# SevSeg-Shield-v10.net
KiCad netlist of a schematic drawn in EAGLE
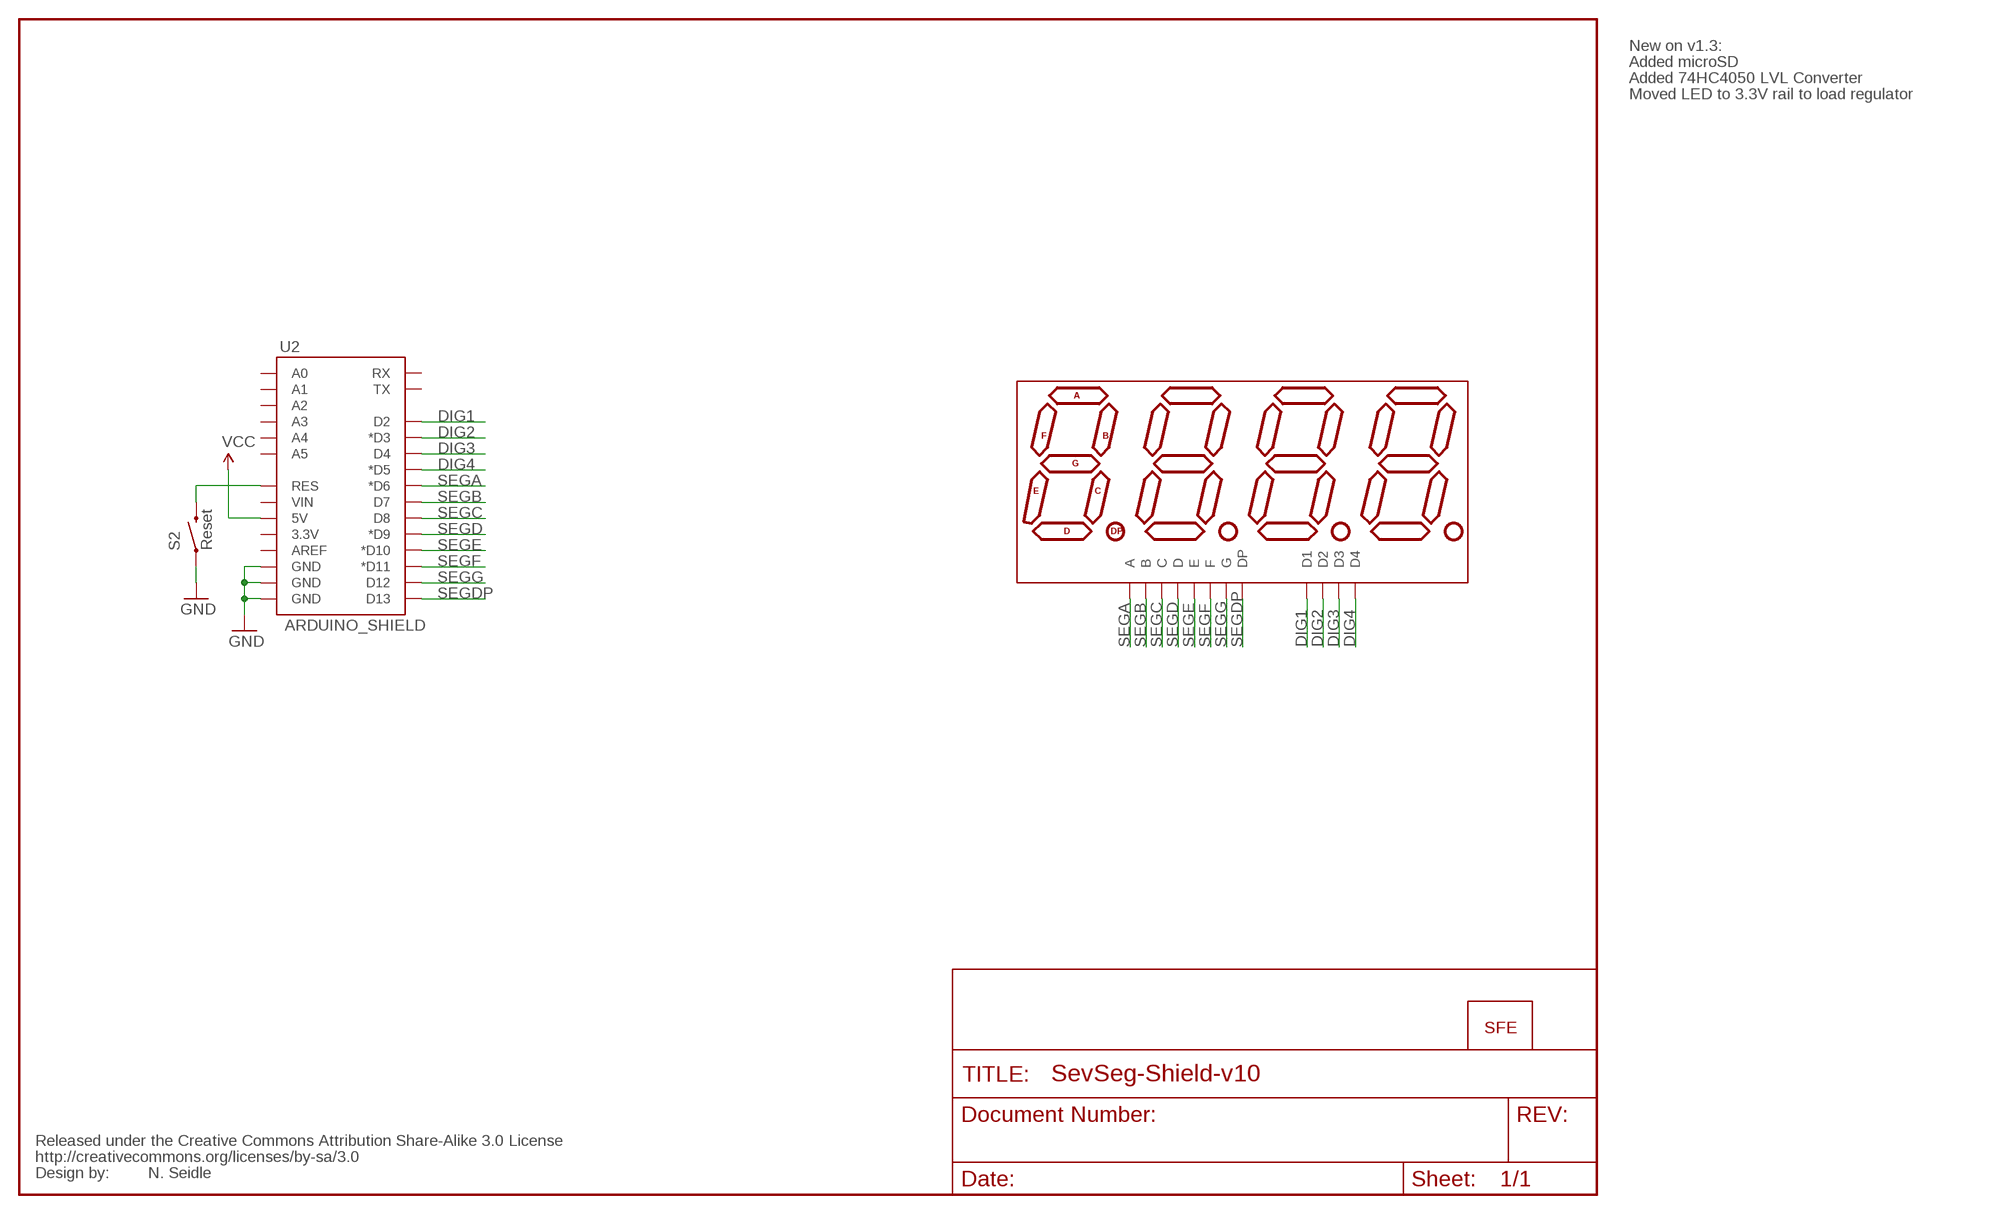
[diagram p0: schematic, sheet 1]

(export (version "E")
  (design (tool "Eeschema 10.0.6"))
  (components
    (comp (ref "S2")
      (value "Reset")
      (footprint "eagle-import:TACTILE-PTH")
      (libsource (lib "eagle-import") (part "SWITCH-MOMENTARY-2PTH"))
    )
    (comp (ref "U$1")
      (value "7-SEGMENT-4DIGIT-COUNTERPTH")
      (footprint "eagle-import:7-SEGMENT-4DIGIT-COUNTER")
      (libsource (lib "eagle-import") (part "7-SEGMENT-4DIGIT-COUNTERPTH"))
    )
    (comp (ref "U$3")
      (value "CREATIVE_COMMONS")
      (footprint "eagle-import:CREATIVE_COMMONS")
      (libsource (lib "eagle-import") (part "CREATIVE_COMMONS"))
    )
    (comp (ref "U$7")
      (value "LOGO-SFENEW")
      (footprint "eagle-import:SFE-NEW-WEBLOGO")
      (libsource (lib "eagle-import") (part "LOGO-SFENEW"))
    )
    (comp (ref "U2")
      (value "ARDUINO_SHIELD")
      (footprint "eagle-import:DUEMILANOVE_SHIELD")
      (libsource (lib "eagle-import") (part "ARDUINO_SHIELDLABEL"))
    )
  )
  (nets
    (net (code "1") (name "/DIG1") (class "Default")
      (node (ref "U$1") (pin "12") (pinfunction "D1_12") (pintype "bidirectional"))
      (node (ref "U2") (pin "D2") (pinfunction "D2_D2") (pintype "bidirectional"))
    )
    (net (code "2") (name "/DIG2") (class "Default")
      (node (ref "U$1") (pin "9") (pinfunction "D2_9") (pintype "bidirectional"))
      (node (ref "U2") (pin "D3") (pinfunction "*D3_D3") (pintype "bidirectional"))
    )
    (net (code "3") (name "/DIG3") (class "Default")
      (node (ref "U$1") (pin "8") (pinfunction "D3_8") (pintype "bidirectional"))
      (node (ref "U2") (pin "D4") (pinfunction "D4_D4") (pintype "bidirectional"))
    )
    (net (code "4") (name "/DIG4") (class "Default")
      (node (ref "U$1") (pin "6") (pinfunction "D4_6") (pintype "bidirectional"))
      (node (ref "U2") (pin "D5") (pinfunction "*D5_D5") (pintype "bidirectional"))
    )
    (net (code "5") (name "/SEGA") (class "Default")
      (node (ref "U$1") (pin "11") (pinfunction "A_11") (pintype "bidirectional"))
      (node (ref "U2") (pin "D6") (pinfunction "*D6_D6") (pintype "bidirectional"))
    )
    (net (code "6") (name "/SEGB") (class "Default")
      (node (ref "U$1") (pin "7") (pinfunction "B_7") (pintype "bidirectional"))
      (node (ref "U2") (pin "D7") (pinfunction "D7_D7") (pintype "bidirectional"))
    )
    (net (code "7") (name "/SEGC") (class "Default")
      (node (ref "U$1") (pin "4") (pinfunction "C_4") (pintype "bidirectional"))
      (node (ref "U2") (pin "D8") (pinfunction "D8_D8") (pintype "bidirectional"))
    )
    (net (code "8") (name "/SEGD") (class "Default")
      (node (ref "U$1") (pin "2") (pinfunction "D_2") (pintype "bidirectional"))
      (node (ref "U2") (pin "D9") (pinfunction "*D9_D9") (pintype "bidirectional"))
    )
    (net (code "9") (name "/SEGDP") (class "Default")
      (node (ref "U$1") (pin "3") (pinfunction "DP_3") (pintype "bidirectional"))
      (node (ref "U2") (pin "D13") (pinfunction "D13_D13") (pintype "bidirectional"))
    )
    (net (code "10") (name "/SEGE") (class "Default")
      (node (ref "U$1") (pin "1") (pinfunction "E_1") (pintype "bidirectional"))
      (node (ref "U2") (pin "D10") (pinfunction "*D10_D10") (pintype "bidirectional"))
    )
    (net (code "11") (name "/SEGF") (class "Default")
      (node (ref "U$1") (pin "10") (pinfunction "F_10") (pintype "bidirectional"))
      (node (ref "U2") (pin "D11") (pinfunction "*D11_D11") (pintype "bidirectional"))
    )
    (net (code "12") (name "/SEGG") (class "Default")
      (node (ref "U$1") (pin "5") (pinfunction "G_5") (pintype "bidirectional"))
      (node (ref "U2") (pin "D12") (pinfunction "D12_D12") (pintype "bidirectional"))
    )
    (net (code "13") (name "GND") (class "Default")
      (node (ref "S2") (pin "1") (pinfunction "1_1") (pintype "passive"))
      (node (ref "U2") (pin "GND@0") (pinfunction "GND_GND@0") (pintype "bidirectional"))
      (node (ref "U2") (pin "GND@1") (pinfunction "GND_GND@1") (pintype "bidirectional"))
      (node (ref "U2") (pin "GND@2") (pinfunction "GND_GND@2") (pintype "bidirectional"))
    )
    (net (code "14") (name "Net-(S2-2)") (class "Default")
      (node (ref "S2") (pin "3") (pinfunction "2_3") (pintype "passive"))
      (node (ref "U2") (pin "RES") (pinfunction "RES_RES") (pintype "bidirectional"))
    )
    (net (code "15") (name "VCC") (class "Default")
      (node (ref "U2") (pin "5V") (pinfunction "5V_5V") (pintype "bidirectional"))
    )
    (net (code "16") (name "unconnected-(U2-Pad3.3V)") (class "Default")
      (node (ref "U2") (pin "3.3V") (pinfunction "3.3V_3.3V") (pintype "bidirectional"))
    )
    (net (code "17") (name "unconnected-(U2-PadA0)") (class "Default")
      (node (ref "U2") (pin "A0") (pinfunction "A0_A0") (pintype "bidirectional"))
    )
    (net (code "18") (name "unconnected-(U2-PadA1)") (class "Default")
      (node (ref "U2") (pin "A1") (pinfunction "A1_A1") (pintype "bidirectional"))
    )
    (net (code "19") (name "unconnected-(U2-PadA2)") (class "Default")
      (node (ref "U2") (pin "A2") (pinfunction "A2_A2") (pintype "bidirectional"))
    )
    (net (code "20") (name "unconnected-(U2-PadA3)") (class "Default")
      (node (ref "U2") (pin "A3") (pinfunction "A3_A3") (pintype "bidirectional"))
    )
    (net (code "21") (name "unconnected-(U2-PadA4)") (class "Default")
      (node (ref "U2") (pin "A4") (pinfunction "A4_A4") (pintype "bidirectional"))
    )
    (net (code "22") (name "unconnected-(U2-PadA5)") (class "Default")
      (node (ref "U2") (pin "A5") (pinfunction "A5_A5") (pintype "bidirectional"))
    )
    (net (code "23") (name "unconnected-(U2-PadAREF)") (class "Default")
      (node (ref "U2") (pin "AREF") (pinfunction "AREF_AREF") (pintype "bidirectional"))
    )
    (net (code "24") (name "unconnected-(U2-PadRX)") (class "Default")
      (node (ref "U2") (pin "RX") (pinfunction "RX_RX") (pintype "bidirectional"))
    )
    (net (code "25") (name "unconnected-(U2-PadTX)") (class "Default")
      (node (ref "U2") (pin "TX") (pinfunction "TX_TX") (pintype "bidirectional"))
    )
    (net (code "26") (name "unconnected-(U2-PadVIN)") (class "Default")
      (node (ref "U2") (pin "VIN") (pinfunction "VIN_VIN") (pintype "bidirectional"))
    )
  )
)
